# Transformer_Stage.net
KiCad netlist of a schematic drawn in Altium Designer
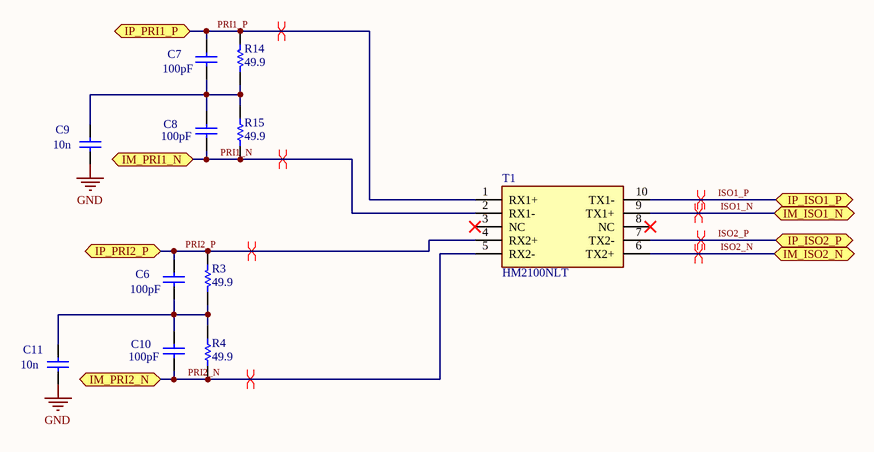
[diagram p0: Transformer_Stage.SchDoc]

(export (version "E")
  (design (tool "Eeschema 10.0.6"))
  (components
    (comp (ref "C6")
      (value "100pF")
      (footprint "0603 - Capacitor")
      (description "Nonpolarized Capacitor")
      (fields (field (name "Comment") "Capacitor - Nonpolarized"))
      (libsource (lib "General") (part "Capacitor - Nonpolarized"))
    )
    (comp (ref "C7")
      (value "100pF")
      (footprint "0603 - Capacitor")
      (description "Nonpolarized Capacitor")
      (fields (field (name "Comment") "Capacitor - Nonpolarized"))
      (libsource (lib "General") (part "Capacitor - Nonpolarized"))
    )
    (comp (ref "C8")
      (value "100pF")
      (footprint "0603 - Capacitor")
      (description "Nonpolarized Capacitor")
      (fields (field (name "Comment") "Capacitor - Nonpolarized"))
      (libsource (lib "General") (part "Capacitor - Nonpolarized"))
    )
    (comp (ref "C9")
      (value "10n")
      (footprint "0603 - Capacitor")
      (description "Nonpolarized Capacitor")
      (fields (field (name "Comment") "Capacitor - Nonpolarized"))
      (libsource (lib "General") (part "Capacitor - Nonpolarized"))
    )
    (comp (ref "C10")
      (value "100pF")
      (footprint "0603 - Capacitor")
      (description "Nonpolarized Capacitor")
      (fields (field (name "Comment") "Capacitor - Nonpolarized"))
      (libsource (lib "General") (part "Capacitor - Nonpolarized"))
    )
    (comp (ref "C11")
      (value "10n")
      (footprint "0603 - Capacitor")
      (description "Nonpolarized Capacitor")
      (fields (field (name "Comment") "Capacitor - Nonpolarized"))
      (libsource (lib "General") (part "Capacitor - Nonpolarized"))
    )
    (comp (ref "R3")
      (value "49.9")
      (footprint "0603 - Resistor")
      (description "Resistor")
      (libsource (lib "General") (part "Resistor"))
    )
    (comp (ref "R4")
      (value "49.9")
      (footprint "0603 - Resistor")
      (description "Resistor")
      (libsource (lib "General") (part "Resistor"))
    )
    (comp (ref "R14")
      (value "49.9")
      (footprint "0603 - Resistor")
      (description "Resistor")
      (libsource (lib "General") (part "Resistor"))
    )
    (comp (ref "R15")
      (value "49.9")
      (footprint "0603 - Resistor")
      (description "Resistor")
      (libsource (lib "General") (part "Resistor"))
    )
    (comp (ref "T1")
      (value "HM2100NLT")
      (footprint "HM2100NLT")
      (description "Pulse Transformer 1:1 Surface Mount 150µH, 450µH")
      (fields (field (name "MANUFACTURER") "Pulse Electronics"))
      (libsource (lib "GeneralComponents") (part "HM2100NLT"))
    )
  )
  (nets
    (net (code "1") (name "/ISO1_N") (class "Default")
      (node (ref "T1") (pin "9") (pinfunction "TX1+_9") (pintype "passive"))
    )
    (net (code "2") (name "/ISO1_P") (class "Default")
      (node (ref "T1") (pin "10") (pinfunction "TX1-_10") (pintype "passive"))
    )
    (net (code "3") (name "/ISO2_N") (class "Default")
      (node (ref "T1") (pin "6") (pinfunction "TX2+_6") (pintype "passive"))
    )
    (net (code "4") (name "/ISO2_P") (class "Default")
      (node (ref "T1") (pin "7") (pinfunction "TX2-_7") (pintype "passive"))
    )
    (net (code "5") (name "/PRI1_N") (class "Default")
      (node (ref "C8") (pin "2") (pinfunction "2_2") (pintype "passive"))
      (node (ref "R15") (pin "1") (pinfunction "1_1") (pintype "passive"))
      (node (ref "T1") (pin "2") (pinfunction "RX1-_2") (pintype "passive"))
    )
    (net (code "6") (name "/PRI1_P") (class "Default")
      (node (ref "C7") (pin "1") (pinfunction "1_1") (pintype "passive"))
      (node (ref "R14") (pin "1") (pinfunction "1_1") (pintype "passive"))
      (node (ref "T1") (pin "1") (pinfunction "RX1+_1") (pintype "passive"))
    )
    (net (code "7") (name "/PRI2_N") (class "Default")
      (node (ref "C10") (pin "2") (pinfunction "2_2") (pintype "passive"))
      (node (ref "R4") (pin "1") (pinfunction "1_1") (pintype "passive"))
      (node (ref "T1") (pin "5") (pinfunction "RX2-_5") (pintype "passive"))
    )
    (net (code "8") (name "/PRI2_P") (class "Default")
      (node (ref "C6") (pin "1") (pinfunction "1_1") (pintype "passive"))
      (node (ref "R3") (pin "1") (pinfunction "1_1") (pintype "passive"))
      (node (ref "T1") (pin "4") (pinfunction "RX2+_4") (pintype "passive"))
    )
    (net (code "9") (name "GND") (class "Default")
      (node (ref "C11") (pin "2") (pinfunction "2_2") (pintype "passive"))
      (node (ref "C9") (pin "2") (pinfunction "2_2") (pintype "passive"))
    )
    (net (code "10") (name "Net-(C7-Pad2)") (class "Default")
      (node (ref "C7") (pin "2") (pinfunction "2_2") (pintype "passive"))
      (node (ref "C8") (pin "1") (pinfunction "1_1") (pintype "passive"))
      (node (ref "C9") (pin "1") (pinfunction "1_1") (pintype "passive"))
      (node (ref "R14") (pin "2") (pinfunction "2_2") (pintype "passive"))
      (node (ref "R15") (pin "2") (pinfunction "2_2") (pintype "passive"))
    )
    (net (code "11") (name "Net-(C10-Pad1)") (class "Default")
      (node (ref "C10") (pin "1") (pinfunction "1_1") (pintype "passive"))
      (node (ref "C11") (pin "1") (pinfunction "1_1") (pintype "passive"))
      (node (ref "C6") (pin "2") (pinfunction "2_2") (pintype "passive"))
      (node (ref "R3") (pin "2") (pinfunction "2_2") (pintype "passive"))
      (node (ref "R4") (pin "2") (pinfunction "2_2") (pintype "passive"))
    )
    (net (code "12") (name "unconnected-(T1-NC-Pad3)") (class "Default")
      (node (ref "T1") (pin "3") (pinfunction "NC_3") (pintype "passive+no_connect"))
    )
    (net (code "13") (name "unconnected-(T1-NC-Pad8)") (class "Default")
      (node (ref "T1") (pin "8") (pinfunction "NC_8") (pintype "passive+no_connect"))
    )
  )
)
